# Interface_Protection.net
KiCad netlist of a schematic drawn in Altium Designer
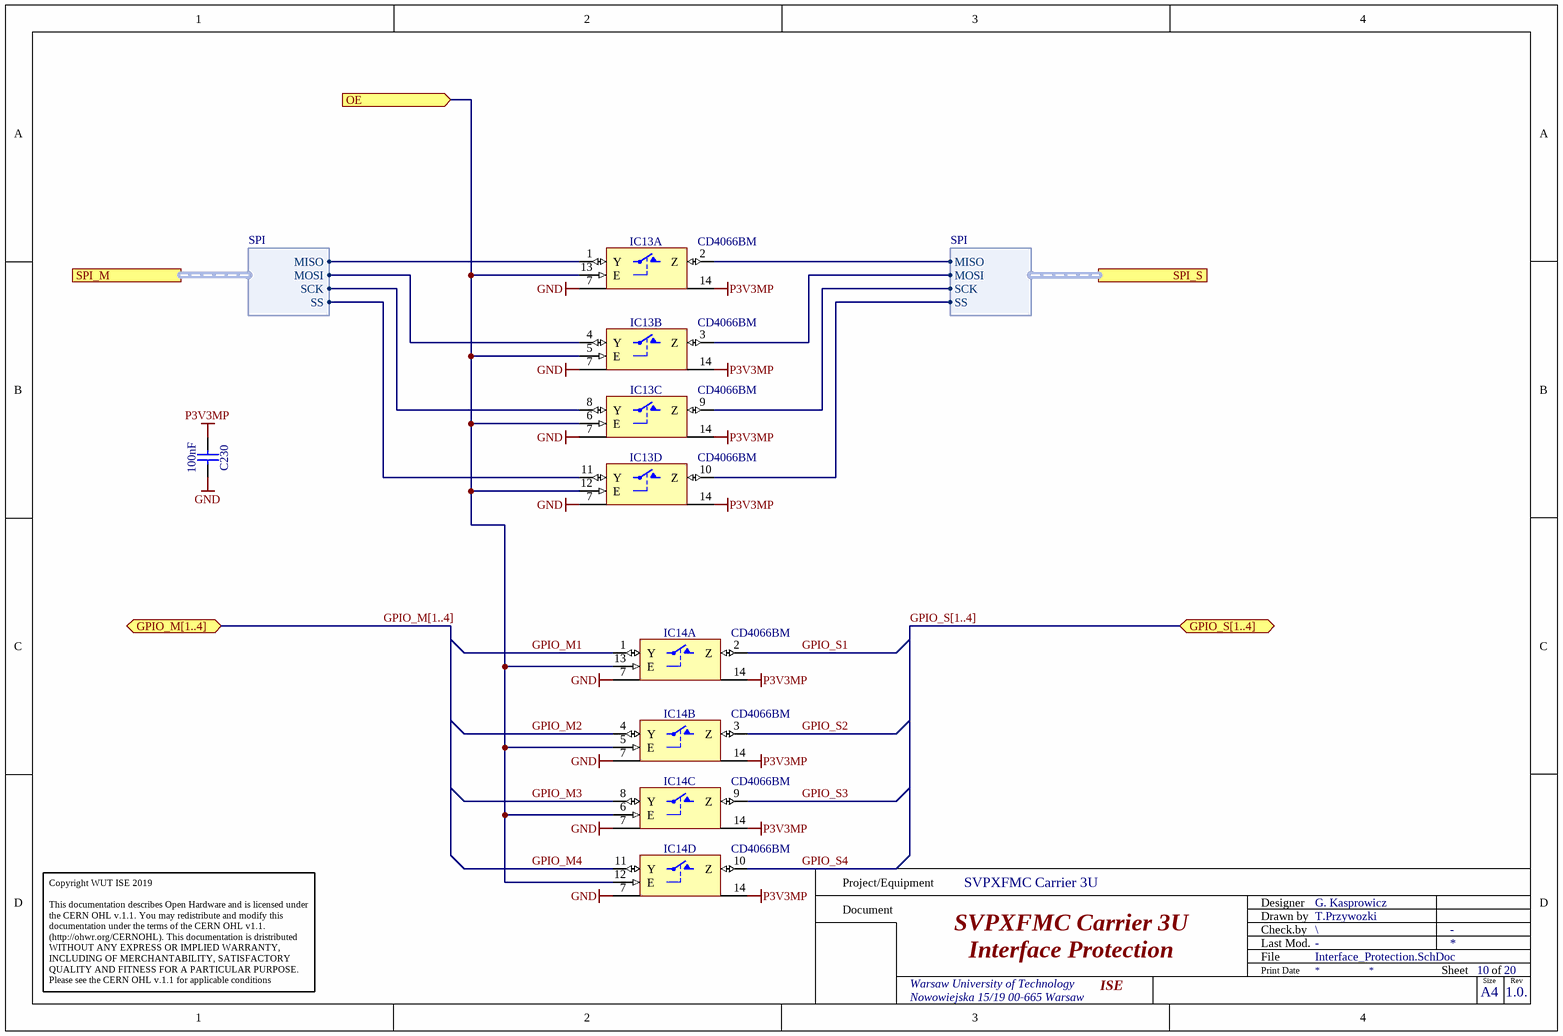
[diagram p0: Interface_Protection.SchDoc]

(export (version "E")
  (design (tool "Eeschema 10.0.6"))
  (components
    (comp (ref "C230")
      (value "100nF")
      (footprint "CAPC1005X55N")
      (description "Non-polarised capacitor")
      (fields
        (field (name "PART NUMBER") "CC0402_100NF_25V_10%_X7R_YUDEN_TMK105B7104KVHF")
        (field (name "VOLTAGE") "25V")
        (field (name "AUTHOR") "CERN DEM JLC")
      )
      (libsource (lib "Capacitors") (part "Capacitor - non polarized"))
    )
    (comp (ref "IC13")
      (value "CD4066BM")
      (footprint "SOIC127P600X175-14N")
      (fields (field (name "MANUFACTURER") "TEXAS INSTRUMENTS") (field (name "AUTHOR") "CERN DEM MR"))
      (libsource (lib "ICs And Semiconductors") (part "4066_a"))
    )
    (comp (ref "IC14")
      (value "CD4066BM")
      (footprint "SOIC127P600X175-14N")
      (fields (field (name "MANUFACTURER") "TEXAS INSTRUMENTS") (field (name "AUTHOR") "CERN DEM MR"))
      (libsource (lib "ICs And Semiconductors") (part "4066_a"))
    )
  )
  (nets
    (net (code "2") (name "/GPIO_M1") (class "Default")
      (node (ref "IC14") (pin "1") (pinfunction "Y_1") (pintype "bidirectional"))
    )
    (net (code "3") (name "/GPIO_M2") (class "Default")
      (node (ref "IC14") (pin "4") (pinfunction "Y_4") (pintype "bidirectional"))
    )
    (net (code "4") (name "/GPIO_M3") (class "Default")
      (node (ref "IC14") (pin "8") (pinfunction "Y_8") (pintype "bidirectional"))
    )
    (net (code "5") (name "/GPIO_M4") (class "Default")
      (node (ref "IC14") (pin "11") (pinfunction "Y_11") (pintype "bidirectional"))
    )
    (net (code "7") (name "/GPIO_S1") (class "Default")
      (node (ref "IC14") (pin "2") (pinfunction "Z_2") (pintype "bidirectional"))
    )
    (net (code "8") (name "/GPIO_S2") (class "Default")
      (node (ref "IC14") (pin "3") (pinfunction "Z_3") (pintype "bidirectional"))
    )
    (net (code "9") (name "/GPIO_S3") (class "Default")
      (node (ref "IC14") (pin "9") (pinfunction "Z_9") (pintype "bidirectional"))
    )
    (net (code "10") (name "/GPIO_S4") (class "Default")
      (node (ref "IC14") (pin "10") (pinfunction "Z_10") (pintype "bidirectional"))
    )
    (net (code "12") (name "/OE") (class "Default")
      (node (ref "IC13") (pin "12") (pinfunction "E_12") (pintype "input"))
      (node (ref "IC13") (pin "13") (pinfunction "E_13") (pintype "input"))
      (node (ref "IC13") (pin "5") (pinfunction "E_5") (pintype "input"))
      (node (ref "IC13") (pin "6") (pinfunction "E_6") (pintype "input"))
      (node (ref "IC14") (pin "12") (pinfunction "E_12") (pintype "input"))
      (node (ref "IC14") (pin "13") (pinfunction "E_13") (pintype "input"))
      (node (ref "IC14") (pin "5") (pinfunction "E_5") (pintype "input"))
      (node (ref "IC14") (pin "6") (pinfunction "E_6") (pintype "input"))
    )
    (net (code "14") (name "GND") (class "Default")
      (node (ref "C230") (pin "2") (pinfunction "2_2") (pintype "passive"))
      (node (ref "IC13") (pin "7") (pinfunction "VSS_7") (pintype "power_in"))
      (node (ref "IC14") (pin "7") (pinfunction "VSS_7") (pintype "power_in"))
    )
    (net (code "15") (name "P3V3MP") (class "Default")
      (node (ref "C230") (pin "1") (pinfunction "1_1") (pintype "passive"))
      (node (ref "IC13") (pin "14") (pinfunction "VDD_14") (pintype "power_in"))
      (node (ref "IC14") (pin "14") (pinfunction "VDD_14") (pintype "power_in"))
    )
    (net (code "16") (name "unconnected-(IC13A-Y-Pad1)") (class "Default")
      (node (ref "IC13") (pin "1") (pinfunction "Y_1") (pintype "bidirectional"))
    )
    (net (code "17") (name "unconnected-(IC13A-Z-Pad2)") (class "Default")
      (node (ref "IC13") (pin "2") (pinfunction "Z_2") (pintype "bidirectional"))
    )
    (net (code "18") (name "unconnected-(IC13B-Y-Pad4)") (class "Default")
      (node (ref "IC13") (pin "4") (pinfunction "Y_4") (pintype "bidirectional"))
    )
    (net (code "19") (name "unconnected-(IC13B-Z-Pad3)") (class "Default")
      (node (ref "IC13") (pin "3") (pinfunction "Z_3") (pintype "bidirectional"))
    )
    (net (code "20") (name "unconnected-(IC13C-Y-Pad8)") (class "Default")
      (node (ref "IC13") (pin "8") (pinfunction "Y_8") (pintype "bidirectional"))
    )
    (net (code "21") (name "unconnected-(IC13C-Z-Pad9)") (class "Default")
      (node (ref "IC13") (pin "9") (pinfunction "Z_9") (pintype "bidirectional"))
    )
    (net (code "22") (name "unconnected-(IC13D-Y-Pad11)") (class "Default")
      (node (ref "IC13") (pin "11") (pinfunction "Y_11") (pintype "bidirectional"))
    )
    (net (code "23") (name "unconnected-(IC13D-Z-Pad10)") (class "Default")
      (node (ref "IC13") (pin "10") (pinfunction "Z_10") (pintype "bidirectional"))
    )
  )
)
